# so08c.net
KiCad netlist of a schematic drawn in EAGLE
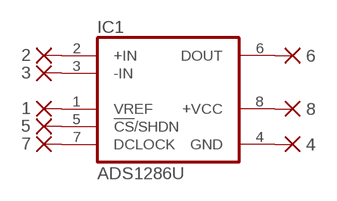
[diagram p0: schematic, sheet 1]

(export (version "E")
  (design (tool "Eeschema 10.0.6"))
  (components
    (comp (ref "1")
      (value "PAD-0360")
      (footprint "eagle-import:0360")
      (libsource (lib "eagle-import") (part "PAD-0360"))
    )
    (comp (ref "2")
      (value "PAD-0360")
      (footprint "eagle-import:0360")
      (libsource (lib "eagle-import") (part "PAD-0360"))
    )
    (comp (ref "3")
      (value "PAD-0360")
      (footprint "eagle-import:0360")
      (libsource (lib "eagle-import") (part "PAD-0360"))
    )
    (comp (ref "4")
      (value "PAD-0360")
      (footprint "eagle-import:0360")
      (libsource (lib "eagle-import") (part "PAD-0360"))
    )
    (comp (ref "5")
      (value "PAD-0360")
      (footprint "eagle-import:0360")
      (libsource (lib "eagle-import") (part "PAD-0360"))
    )
    (comp (ref "6")
      (value "PAD-0360")
      (footprint "eagle-import:0360")
      (libsource (lib "eagle-import") (part "PAD-0360"))
    )
    (comp (ref "7")
      (value "PAD-0360")
      (footprint "eagle-import:0360")
      (libsource (lib "eagle-import") (part "PAD-0360"))
    )
    (comp (ref "8")
      (value "PAD-0360")
      (footprint "eagle-import:0360")
      (libsource (lib "eagle-import") (part "PAD-0360"))
    )
    (comp (ref "IC1")
      (value "ADS1286U")
      (footprint "eagle-import:SO08")
      (fields (field (name "MF") "TEXAS INSTRUMENTS"))
      (libsource (lib "eagle-import") (part "ADS1286U"))
    )
  )
  (nets
    (net (code "1") (name "Net-(1-P)") (class "Default")
      (node (ref "1") (pin "P$1") (pinfunction "P_P$1") (pintype "passive"))
      (node (ref "IC1") (pin "1") (pinfunction "VREF_1") (pintype "input"))
    )
    (net (code "2") (name "Net-(2-P)") (class "Default")
      (node (ref "2") (pin "P$1") (pinfunction "P_P$1") (pintype "passive"))
      (node (ref "IC1") (pin "2") (pinfunction "+IN_2") (pintype "input"))
    )
    (net (code "3") (name "Net-(3-P)") (class "Default")
      (node (ref "3") (pin "P$1") (pinfunction "P_P$1") (pintype "passive"))
      (node (ref "IC1") (pin "3") (pinfunction "-IN_3") (pintype "input"))
    )
    (net (code "4") (name "Net-(4-P)") (class "Default")
      (node (ref "4") (pin "P$1") (pinfunction "P_P$1") (pintype "passive"))
      (node (ref "IC1") (pin "4") (pinfunction "GND_4") (pintype "power_in"))
    )
    (net (code "5") (name "Net-(5-P)") (class "Default")
      (node (ref "5") (pin "P$1") (pinfunction "P_P$1") (pintype "passive"))
      (node (ref "IC1") (pin "5") (pinfunction "~{CS}/SHDN_5") (pintype "input"))
    )
    (net (code "6") (name "Net-(6-P)") (class "Default")
      (node (ref "6") (pin "P$1") (pinfunction "P_P$1") (pintype "passive"))
      (node (ref "IC1") (pin "6") (pinfunction "DOUT_6") (pintype "output"))
    )
    (net (code "7") (name "Net-(7-P)") (class "Default")
      (node (ref "7") (pin "P$1") (pinfunction "P_P$1") (pintype "passive"))
      (node (ref "IC1") (pin "7") (pinfunction "DCLOCK_7") (pintype "input"))
    )
    (net (code "8") (name "Net-(8-P)") (class "Default")
      (node (ref "8") (pin "P$1") (pinfunction "P_P$1") (pintype "passive"))
      (node (ref "IC1") (pin "8") (pinfunction "+VCC_8") (pintype "power_in"))
    )
  )
)
